# Mini_Power_Supply.net
KiCad netlist of a schematic drawn in EAGLE
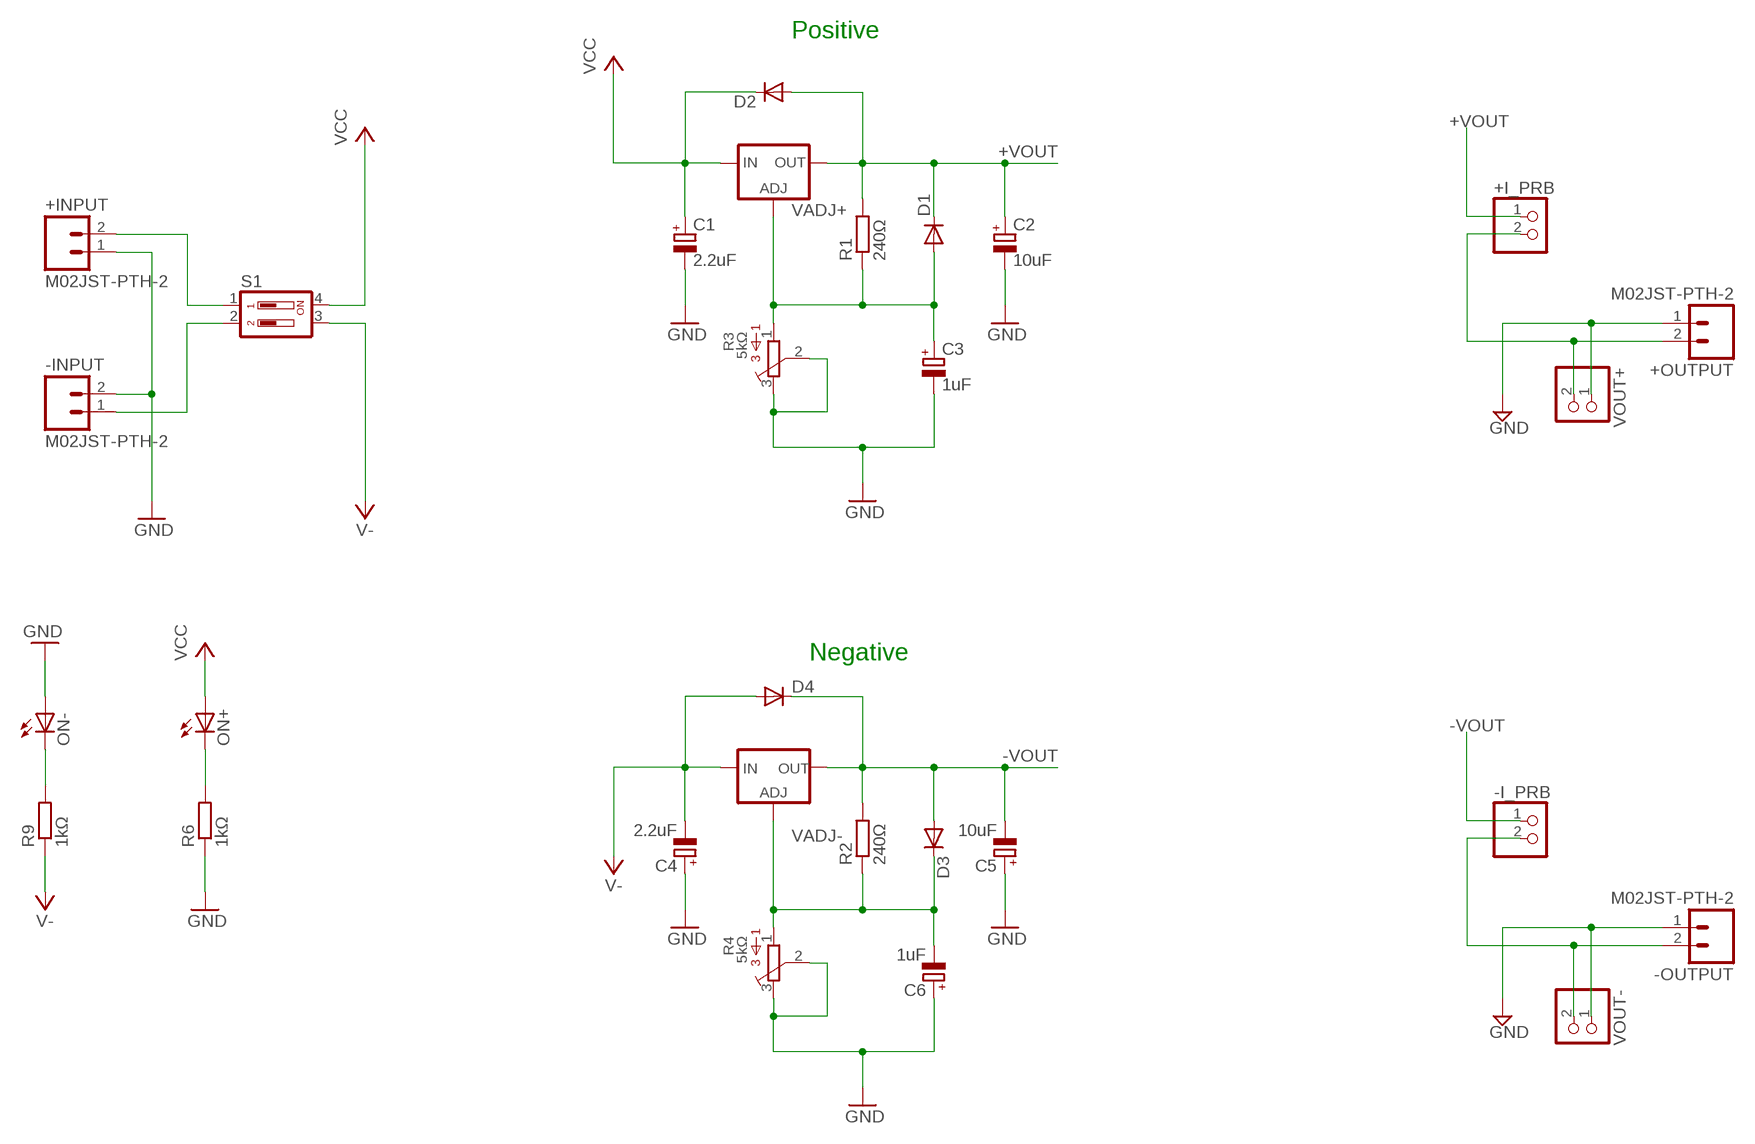
[diagram p0: schematic, sheet 1]

(export (version "E")
  (design (tool "Eeschema 10.0.6"))
  (components
    (comp (ref "+INPUT")
      (value "M02JST-PTH-2")
      (footprint "eagle-import:JST-2-PTH")
      (libsource (lib "eagle-import") (part "M02JST-PTH-2"))
    )
    (comp (ref "+I_PRB")
      (value "PINHD-1X2")
      (footprint "eagle-import:1X02")
      (libsource (lib "eagle-import") (part "PINHD-1X2"))
    )
    (comp (ref "+OUTPUT")
      (value "M02JST-PTH-2")
      (footprint "eagle-import:JST-2-PTH")
      (libsource (lib "eagle-import") (part "M02JST-PTH-2"))
    )
    (comp (ref "-INPUT")
      (value "M02JST-PTH-2")
      (footprint "eagle-import:JST-2-PTH")
      (libsource (lib "eagle-import") (part "M02JST-PTH-2"))
    )
    (comp (ref "-I_PRB")
      (value "PINHD-1X2")
      (footprint "eagle-import:1X02")
      (libsource (lib "eagle-import") (part "PINHD-1X2"))
    )
    (comp (ref "-OUTPUT")
      (value "M02JST-PTH-2")
      (footprint "eagle-import:JST-2-PTH")
      (libsource (lib "eagle-import") (part "M02JST-PTH-2"))
    )
    (comp (ref "C1")
      (value "2.2uF")
      (footprint "eagle-import:E2,5-6")
      (libsource (lib "eagle-import") (part "CPOL-EUE2.5-6"))
    )
    (comp (ref "C2")
      (value "10uF")
      (footprint "eagle-import:E2,5-6")
      (libsource (lib "eagle-import") (part "CPOL-EUE2.5-6"))
    )
    (comp (ref "C3")
      (value "1uF")
      (footprint "eagle-import:E2,5-6")
      (libsource (lib "eagle-import") (part "CPOL-EUE2.5-6"))
    )
    (comp (ref "C4")
      (value "2.2uF")
      (footprint "eagle-import:E2,5-6")
      (libsource (lib "eagle-import") (part "CPOL-EUE2.5-6"))
    )
    (comp (ref "C5")
      (value "10uF")
      (footprint "eagle-import:E2,5-6")
      (libsource (lib "eagle-import") (part "CPOL-EUE2.5-6"))
    )
    (comp (ref "C6")
      (value "1uF")
      (footprint "eagle-import:E2,5-6")
      (libsource (lib "eagle-import") (part "CPOL-EUE2.5-6"))
    )
    (comp (ref "D1")
      (value "1N4148DO35-7")
      (footprint "eagle-import:DO35-7")
      (libsource (lib "eagle-import") (part "1N4148DO35-7"))
    )
    (comp (ref "D2")
      (value "1N4148DO35-7")
      (footprint "eagle-import:DO35-7")
      (libsource (lib "eagle-import") (part "1N4148DO35-7"))
    )
    (comp (ref "D3")
      (value "1N4148DO35-7")
      (footprint "eagle-import:DO35-7")
      (libsource (lib "eagle-import") (part "1N4148DO35-7"))
    )
    (comp (ref "D4")
      (value "1N4148DO35-7")
      (footprint "eagle-import:DO35-7")
      (libsource (lib "eagle-import") (part "1N4148DO35-7"))
    )
    (comp (ref "ON+")
      (value "LEDSQR2X5")
      (footprint "eagle-import:LED2X5")
      (libsource (lib "eagle-import") (part "LEDSQR2X5"))
    )
    (comp (ref "ON-")
      (value "LEDSQR2X5")
      (footprint "eagle-import:LED2X5")
      (libsource (lib "eagle-import") (part "LEDSQR2X5"))
    )
    (comp (ref "R1")
      (value "240Ω")
      (footprint "eagle-import:0207_10")
      (libsource (lib "eagle-import") (part "R-EU_0207/10"))
    )
    (comp (ref "R2")
      (value "240Ω")
      (footprint "eagle-import:0207_10")
      (libsource (lib "eagle-import") (part "R-EU_0207/10"))
    )
    (comp (ref "R3")
      (value "5kΩ")
      (footprint "eagle-import:3386U")
      (libsource (lib "eagle-import") (part "3386-U"))
    )
    (comp (ref "R4")
      (value "5kΩ")
      (footprint "eagle-import:3386U")
      (libsource (lib "eagle-import") (part "3386-U"))
    )
    (comp (ref "R6")
      (value "1kΩ")
      (footprint "eagle-import:0207_10")
      (libsource (lib "eagle-import") (part "R-EU_0207/10"))
    )
    (comp (ref "R9")
      (value "1kΩ")
      (footprint "eagle-import:0207_10")
      (libsource (lib "eagle-import") (part "R-EU_0207/10"))
    )
    (comp (ref "S1")
      (value "DIP02YL")
      (footprint "eagle-import:DIP02YL")
      (libsource (lib "eagle-import") (part "DIP02YL"))
    )
    (comp (ref "VADJ+")
      (value "LM317L")
      (footprint "eagle-import:317L")
      (libsource (lib "eagle-import") (part "LM317L"))
    )
    (comp (ref "VADJ-")
      (value "LM337L")
      (footprint "eagle-import:337L")
      (libsource (lib "eagle-import") (part "LM337L"))
    )
    (comp (ref "VOUT+")
      (value "PINHD-1X2")
      (footprint "eagle-import:1X02")
      (libsource (lib "eagle-import") (part "PINHD-1X2"))
    )
    (comp (ref "VOUT-")
      (value "PINHD-1X2")
      (footprint "eagle-import:1X02")
      (libsource (lib "eagle-import") (part "PINHD-1X2"))
    )
  )
  (nets
    (net (code "1") (name "/+VOUT") (class "Default")
      (node (ref "+I_PRB") (pin "1") (pinfunction "1_1") (pintype "passive"))
      (node (ref "C2") (pin "+") (pinfunction "+_+") (pintype "passive"))
      (node (ref "D1") (pin "C") (pinfunction "C_C") (pintype "passive"))
      (node (ref "D2") (pin "A") (pinfunction "A_A") (pintype "passive"))
      (node (ref "R1") (pin "2") (pinfunction "2_2") (pintype "passive"))
      (node (ref "VADJ+") (pin "2") (pinfunction "OUT_2") (pintype "passive"))
    )
    (net (code "2") (name "/-VOUT") (class "Default")
      (node (ref "-I_PRB") (pin "1") (pinfunction "1_1") (pintype "passive"))
      (node (ref "C5") (pin "-") (pinfunction "-_-") (pintype "passive"))
      (node (ref "D3") (pin "A") (pinfunction "A_A") (pintype "passive"))
      (node (ref "D4") (pin "C") (pinfunction "C_C") (pintype "passive"))
      (node (ref "R2") (pin "2") (pinfunction "2_2") (pintype "passive"))
      (node (ref "VADJ-") (pin "OUT") (pinfunction "OUT_OUT") (pintype "passive"))
    )
    (net (code "3") (name "GND") (class "Default")
      (node (ref "+INPUT") (pin "1") (pinfunction "1_1") (pintype "passive"))
      (node (ref "+OUTPUT") (pin "1") (pinfunction "1_1") (pintype "passive"))
      (node (ref "-INPUT") (pin "2") (pinfunction "2_2") (pintype "passive"))
      (node (ref "-OUTPUT") (pin "1") (pinfunction "1_1") (pintype "passive"))
      (node (ref "C1") (pin "-") (pinfunction "-_-") (pintype "passive"))
      (node (ref "C2") (pin "-") (pinfunction "-_-") (pintype "passive"))
      (node (ref "C3") (pin "-") (pinfunction "-_-") (pintype "passive"))
      (node (ref "C4") (pin "+") (pinfunction "+_+") (pintype "passive"))
      (node (ref "C5") (pin "+") (pinfunction "+_+") (pintype "passive"))
      (node (ref "C6") (pin "+") (pinfunction "+_+") (pintype "passive"))
      (node (ref "ON-") (pin "A") (pinfunction "A_A") (pintype "passive"))
      (node (ref "R3") (pin "2") (pinfunction "2_2") (pintype "passive"))
      (node (ref "R3") (pin "3") (pinfunction "3_3") (pintype "passive"))
      (node (ref "R4") (pin "2") (pinfunction "2_2") (pintype "passive"))
      (node (ref "R4") (pin "3") (pinfunction "3_3") (pintype "passive"))
      (node (ref "R6") (pin "1") (pinfunction "1_1") (pintype "passive"))
      (node (ref "VOUT+") (pin "1") (pinfunction "1_1") (pintype "passive"))
      (node (ref "VOUT-") (pin "1") (pinfunction "1_1") (pintype "passive"))
    )
    (net (code "4") (name "Net-(+INPUT-Pad2)") (class "Default")
      (node (ref "+INPUT") (pin "2") (pinfunction "2_2") (pintype "passive"))
      (node (ref "S1") (pin "1") (pinfunction "1_1") (pintype "passive"))
    )
    (net (code "5") (name "Net-(+I_PRB-Pad2)") (class "Default")
      (node (ref "+I_PRB") (pin "2") (pinfunction "2_2") (pintype "passive"))
      (node (ref "+OUTPUT") (pin "2") (pinfunction "2_2") (pintype "passive"))
      (node (ref "VOUT+") (pin "2") (pinfunction "2_2") (pintype "passive"))
    )
    (net (code "6") (name "Net-(-INPUT-Pad1)") (class "Default")
      (node (ref "-INPUT") (pin "1") (pinfunction "1_1") (pintype "passive"))
      (node (ref "S1") (pin "2") (pinfunction "2_2") (pintype "passive"))
    )
    (net (code "7") (name "Net-(-I_PRB-Pad2)") (class "Default")
      (node (ref "-I_PRB") (pin "2") (pinfunction "2_2") (pintype "passive"))
      (node (ref "-OUTPUT") (pin "2") (pinfunction "2_2") (pintype "passive"))
      (node (ref "VOUT-") (pin "2") (pinfunction "2_2") (pintype "passive"))
    )
    (net (code "8") (name "Net-(C6-Pad-)") (class "Default")
      (node (ref "C6") (pin "-") (pinfunction "-_-") (pintype "passive"))
      (node (ref "D3") (pin "C") (pinfunction "C_C") (pintype "passive"))
      (node (ref "R2") (pin "1") (pinfunction "1_1") (pintype "passive"))
      (node (ref "R4") (pin "1") (pinfunction "1_1") (pintype "passive"))
      (node (ref "VADJ-") (pin "ADJ") (pinfunction "ADJ_ADJ") (pintype "input"))
    )
    (net (code "9") (name "Net-(ON+-C)") (class "Default")
      (node (ref "ON+") (pin "K") (pinfunction "C_K") (pintype "passive"))
      (node (ref "R6") (pin "2") (pinfunction "2_2") (pintype "passive"))
    )
    (net (code "10") (name "Net-(ON--C)") (class "Default")
      (node (ref "ON-") (pin "K") (pinfunction "C_K") (pintype "passive"))
      (node (ref "R9") (pin "2") (pinfunction "2_2") (pintype "passive"))
    )
    (net (code "11") (name "Net-(VADJ+-ADJ)") (class "Default")
      (node (ref "C3") (pin "+") (pinfunction "+_+") (pintype "passive"))
      (node (ref "D1") (pin "A") (pinfunction "A_A") (pintype "passive"))
      (node (ref "R1") (pin "1") (pinfunction "1_1") (pintype "passive"))
      (node (ref "R3") (pin "1") (pinfunction "1_1") (pintype "passive"))
      (node (ref "VADJ+") (pin "1") (pinfunction "ADJ_1") (pintype "input"))
    )
    (net (code "12") (name "V-") (class "Default")
      (node (ref "C4") (pin "-") (pinfunction "-_-") (pintype "passive"))
      (node (ref "D4") (pin "A") (pinfunction "A_A") (pintype "passive"))
      (node (ref "R9") (pin "1") (pinfunction "1_1") (pintype "passive"))
      (node (ref "S1") (pin "3") (pinfunction "3_3") (pintype "passive"))
      (node (ref "VADJ-") (pin "IN") (pinfunction "IN_IN") (pintype "input"))
    )
    (net (code "13") (name "VCC") (class "Default")
      (node (ref "C1") (pin "+") (pinfunction "+_+") (pintype "passive"))
      (node (ref "D2") (pin "C") (pinfunction "C_C") (pintype "passive"))
      (node (ref "ON+") (pin "A") (pinfunction "A_A") (pintype "passive"))
      (node (ref "S1") (pin "4") (pinfunction "4_4") (pintype "passive"))
      (node (ref "VADJ+") (pin "3") (pinfunction "IN_3") (pintype "input"))
    )
  )
)
